# SH1_-_POWER.net
KiCad netlist of a schematic drawn in Altium Designer
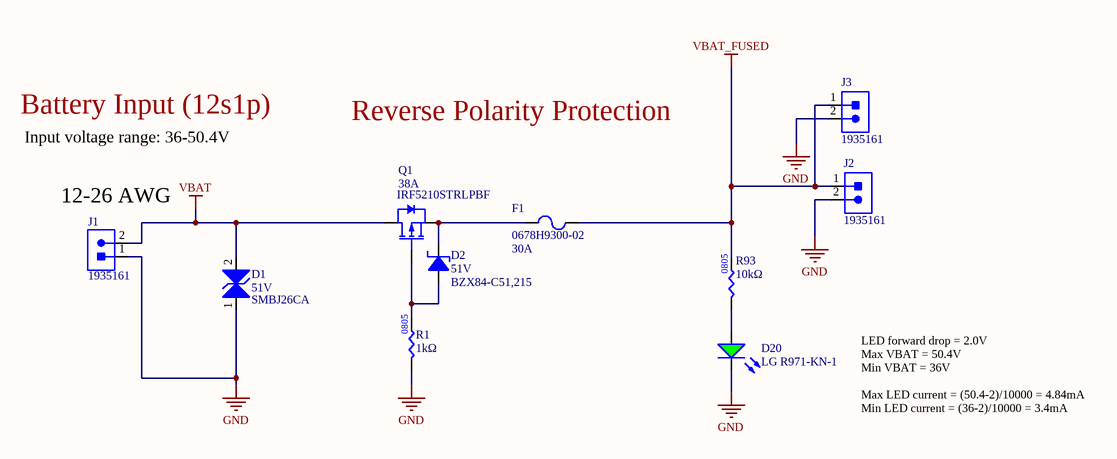
[diagram p0: SH1 - POWER.SchDoc]

(export (version "E")
  (design (tool "Eeschema 10.0.6"))
  (components
    (comp (ref "D1")
      (value "TVS_DIODE_BIDIR_51V")
      (footprint "TVS_DIODE_BIDIR_SMB")
      (description "TVS DIODE 51VWM 82.4VC DO214AA")
      (fields
        (field (name "MANUFACTURER PART NUMBER 1") "SMBJ26CA")
        (field (name "VOLTAGE - REVERSE STANDOFF (TYP)") "51V")
      )
      (libsource (lib "UWRT_Schematic_Library_2020") (part "TVS_DIODE_BIDIR_51V"))
    )
    (comp (ref "D2")
      (value "DIO_ZENER_51V")
      (footprint "SOT23-3")
      (description "DIODE ZENER 51V 250MW TO236AB")
      (fields
        (field (name "MANUFACTURER PART NUMBER 1") "BZX84-C51,215")
        (field (name "WORKING VOLTAGE") "51V")
      )
      (libsource (lib "UWRT_Schematic_Library_2020") (part "DIO_ZENER_51V"))
    )
    (comp (ref "D20")
      (value "LED_GREEN")
      (footprint "LED_0805_GREEN")
      (description "LED GREEN DIFFUSED 0805 SMD")
      (fields (field (name "MANUFACTURER PART NUMBER 1") "LG R971-KN-1"))
      (libsource (lib "UWRT_Schematic_Library_2020") (part "LED_GREEN"))
    )
    (comp (ref "F1")
      (value "FUSE_30A_3912")
      (footprint "FUSE_3912")
      (description "FUSE SMT 3912 ENH BRK 250V 30A")
      (fields
        (field (name "MANUFACTURER PART NUMBER 1") "0678H9300-02")
        (field (name "CURRENT RATING") "30A")
      )
      (libsource (lib "UWRT_Schematic_Library_2020") (part "FUSE_30A_3912"))
    )
    (comp (ref "J1")
      (value "CON_2M_TERM")
      (footprint "1935161")
      (description "TERM BLK 2POS SIDE ENTRY 5MM")
      (fields (field (name "VOLTAGE") "300V") (field (name "MANUFACTURER PART NUMBER 1") "1935161"))
      (libsource (lib "") (part "CON_2M_TERM_1"))
    )
    (comp (ref "J2")
      (value "CON_2M_TERM")
      (footprint "1935161")
      (description "TERM BLK 2POS SIDE ENTRY 5MM")
      (fields (field (name "VOLTAGE") "300V") (field (name "MANUFACTURER PART NUMBER 1") "1935161"))
      (libsource (lib "UWRT_Schematic_Library_2020") (part "CON_2M_TERM"))
    )
    (comp (ref "J3")
      (value "CON_2M_TERM")
      (footprint "1935161")
      (description "TERM BLK 2POS SIDE ENTRY 5MM")
      (fields (field (name "VOLTAGE") "300V") (field (name "MANUFACTURER PART NUMBER 1") "1935161"))
      (libsource (lib "UWRT_Schematic_Library_2020") (part "CON_2M_TERM"))
    )
    (comp (ref "Q1")
      (value "PMOS_100V_38A")
      (footprint "DPAK254P1524X483-4_3N - new")
      (description "MOSFET P-CH 100V 38A D2PAK")
      (fields
        (field (name "CURRENT - CONTINOUS DRAIN") "38A")
        (field (name "MANUFACTURER PART NUMBER 1") "IRF5210STRLPBF")
      )
      (libsource (lib "UWRT_Schematic_Library_2020") (part "PMOS_100V_38A"))
    )
    (comp (ref "R1")
      (value "1kΩ")
      (footprint "RES0805")
      (description "RES 1K OHM 1% 1/8W 0805")
      (fields (field (name "LCSC PART #") "C17513") (field (name "Comment") "RES_1kΩ_0805_1%"))
      (libsource (lib "UWRT_Schematic_Library_2020") (part "RES_1kΩ_0805_1%"))
    )
    (comp (ref "R93")
      (value "10kΩ")
      (footprint "RES0805")
      (description "RES 10K OHM 5% 1/8W 0805")
      (fields (field (name "LCSC PART #") "C17414") (field (name "Comment") "RES_10kΩ_0805_5%"))
      (libsource (lib "UWRT_Schematic_Library_2020") (part "RES_10kΩ_0805_5%"))
    )
  )
  (nets
    (net (code "1") (name "GND") (class "Default")
      (node (ref "D1") (pin "1") (pinfunction "1_1") (pintype "passive"))
      (node (ref "D20") (pin "2") (pinfunction "K_2") (pintype "passive"))
      (node (ref "J1") (pin "1") (pinfunction "1_1") (pintype "passive"))
      (node (ref "J2") (pin "2") (pinfunction "2_2") (pintype "passive"))
      (node (ref "J3") (pin "2") (pinfunction "2_2") (pintype "passive"))
      (node (ref "R1") (pin "1") (pinfunction "1_1") (pintype "passive"))
    )
    (net (code "2") (name "Net-(D2-Anode)") (class "Default")
      (node (ref "D2") (pin "1") (pinfunction "Anode_1") (pintype "passive"))
      (node (ref "Q1") (pin "1") (pinfunction "Gate_1") (pintype "passive"))
      (node (ref "R1") (pin "2") (pinfunction "2_2") (pintype "passive"))
    )
    (net (code "3") (name "Net-(D2-Cathode)") (class "Default")
      (node (ref "D2") (pin "3") (pinfunction "Cathode_3") (pintype "passive"))
      (node (ref "F1") (pin "1") (pinfunction "1_1") (pintype "passive"))
      (node (ref "Q1") (pin "3") (pinfunction "Source_3") (pintype "passive"))
    )
    (net (code "4") (name "Net-(D20-A)") (class "Default")
      (node (ref "D20") (pin "1") (pinfunction "A_1") (pintype "passive"))
      (node (ref "R93") (pin "1") (pinfunction "1_1") (pintype "passive"))
    )
    (net (code "5") (name "VBAT") (class "Default")
      (node (ref "D1") (pin "2") (pinfunction "2_2") (pintype "passive"))
      (node (ref "J1") (pin "2") (pinfunction "2_2") (pintype "passive"))
      (node (ref "Q1") (pin "2") (pinfunction "Drain_2") (pintype "passive"))
    )
    (net (code "6") (name "VBAT_FUSED") (class "Default")
      (node (ref "F1") (pin "2") (pinfunction "2_2") (pintype "passive"))
      (node (ref "J2") (pin "1") (pinfunction "1_1") (pintype "passive"))
      (node (ref "J3") (pin "1") (pinfunction "1_1") (pintype "passive"))
      (node (ref "R93") (pin "2") (pinfunction "2_2") (pintype "passive"))
    )
  )
)
